# mainboard.net
KiCad netlist of a schematic drawn in EAGLE
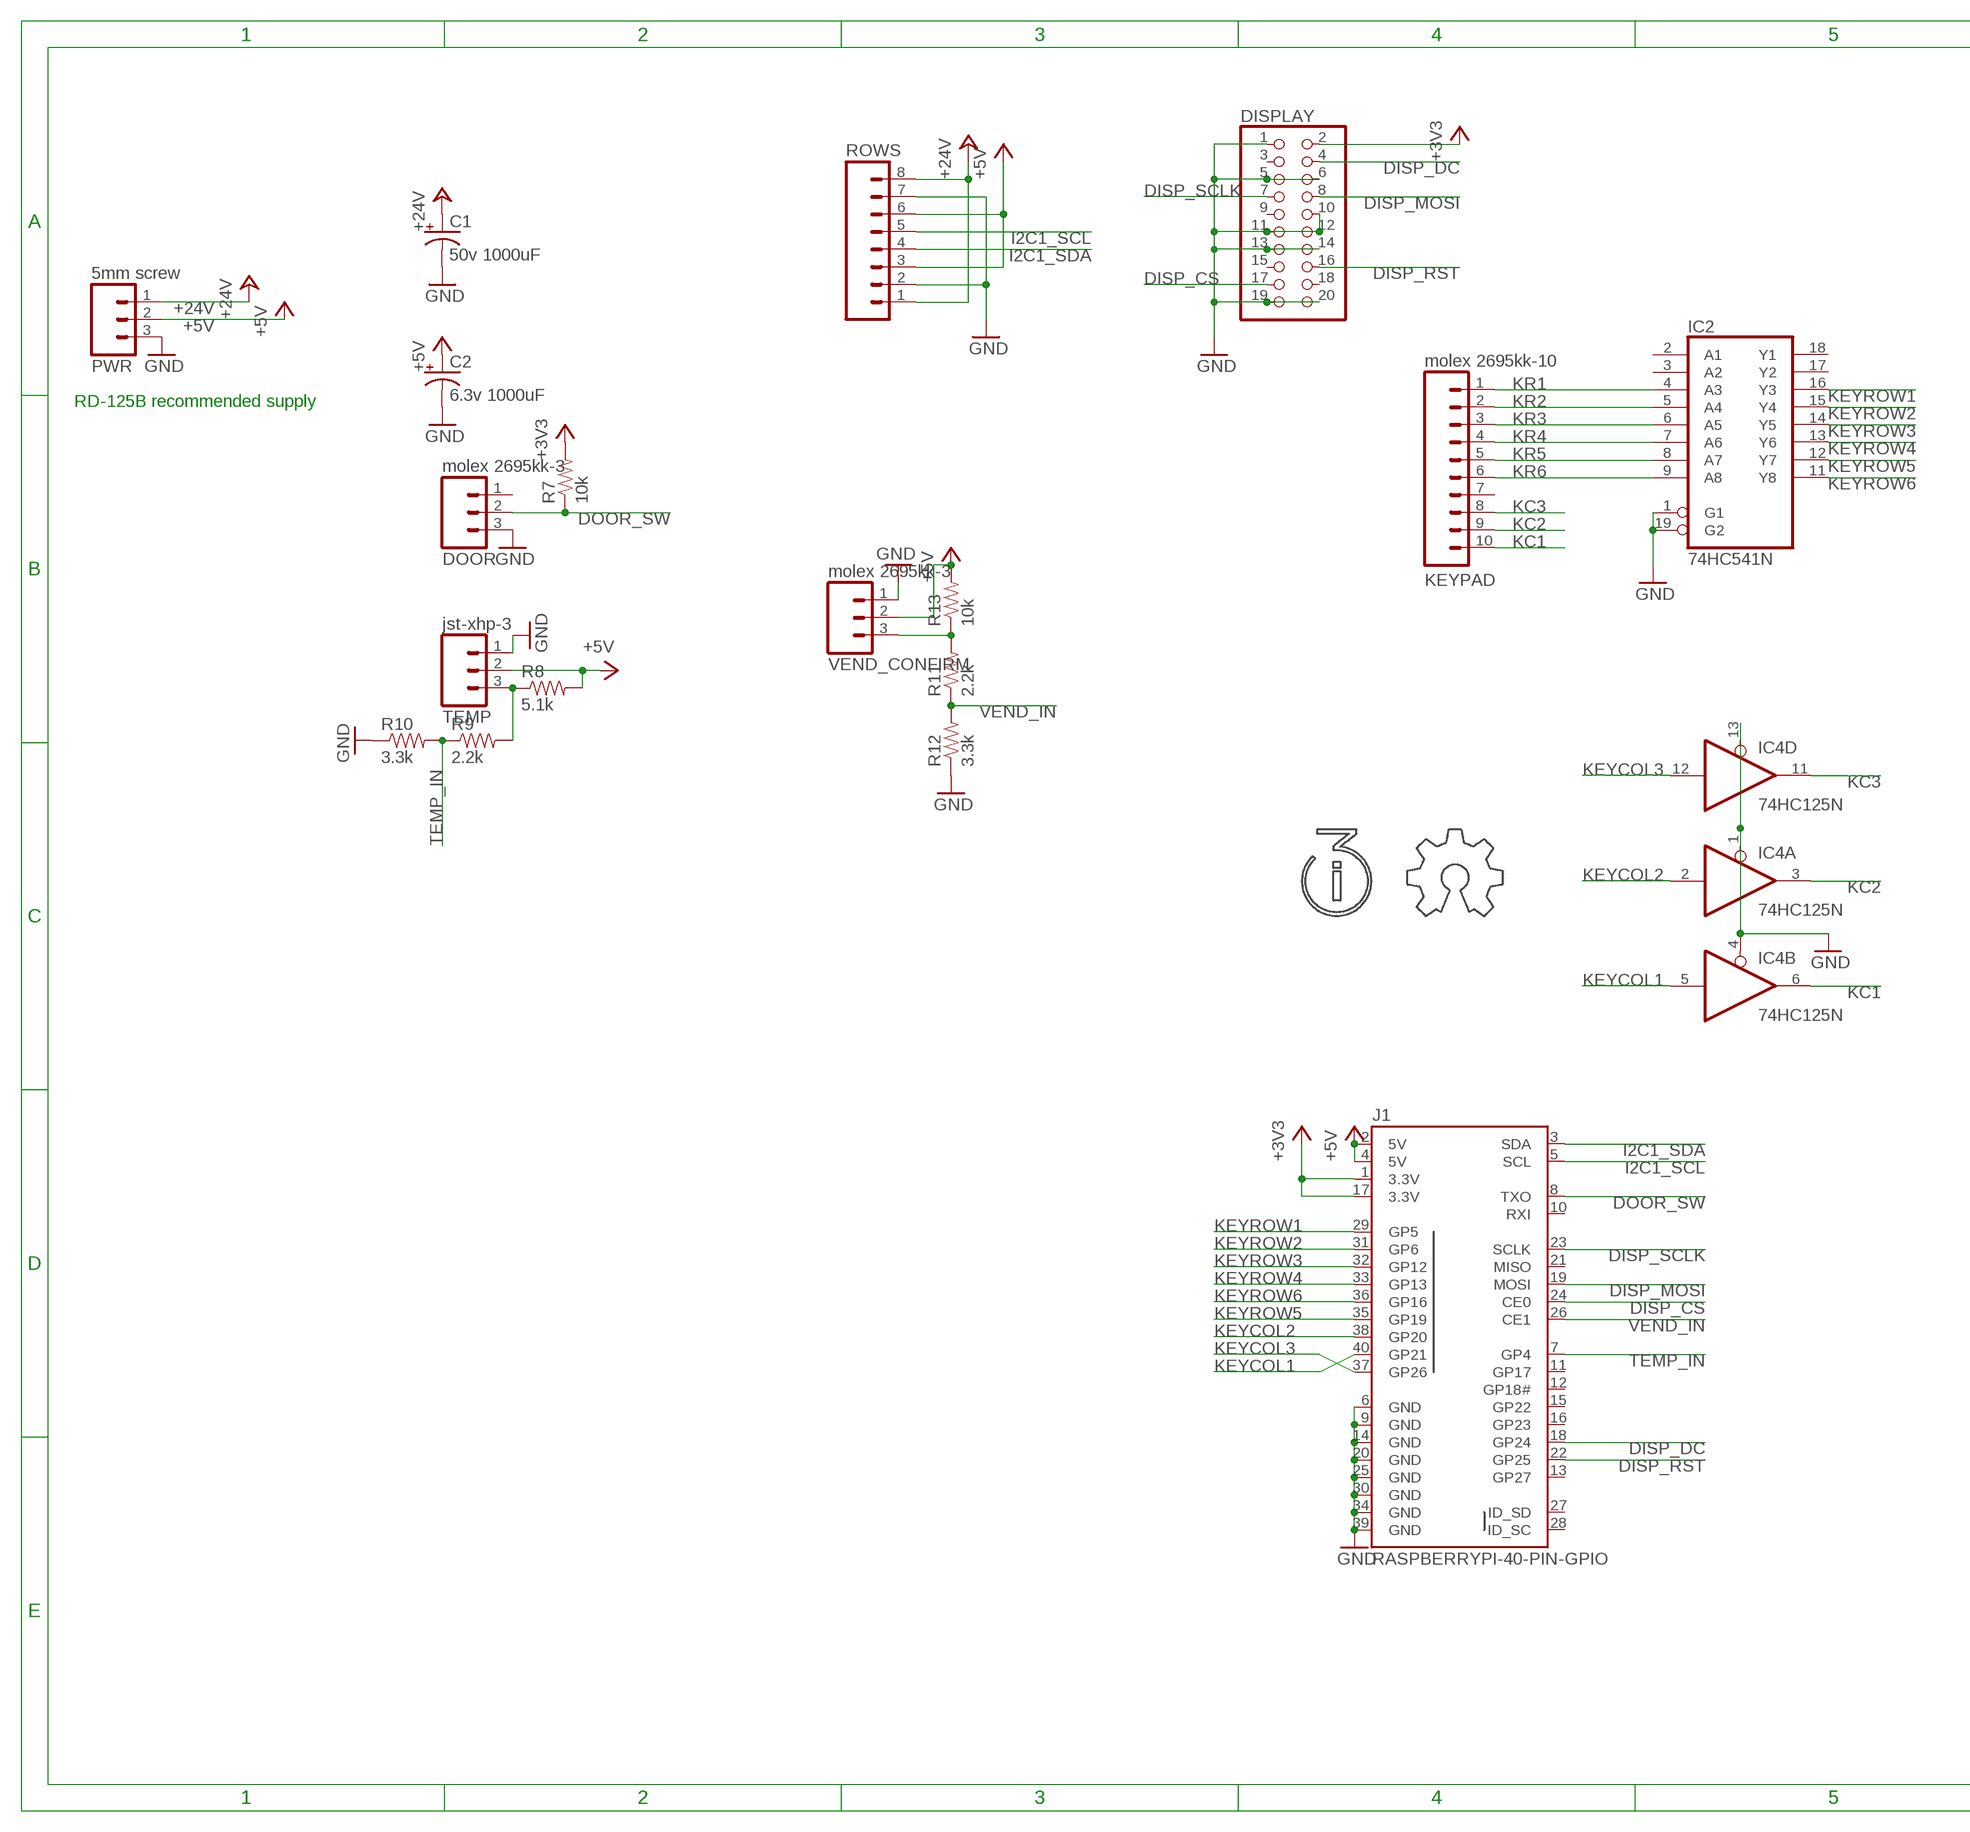
[diagram p0: schematic, sheet 1, part 1 of 2]
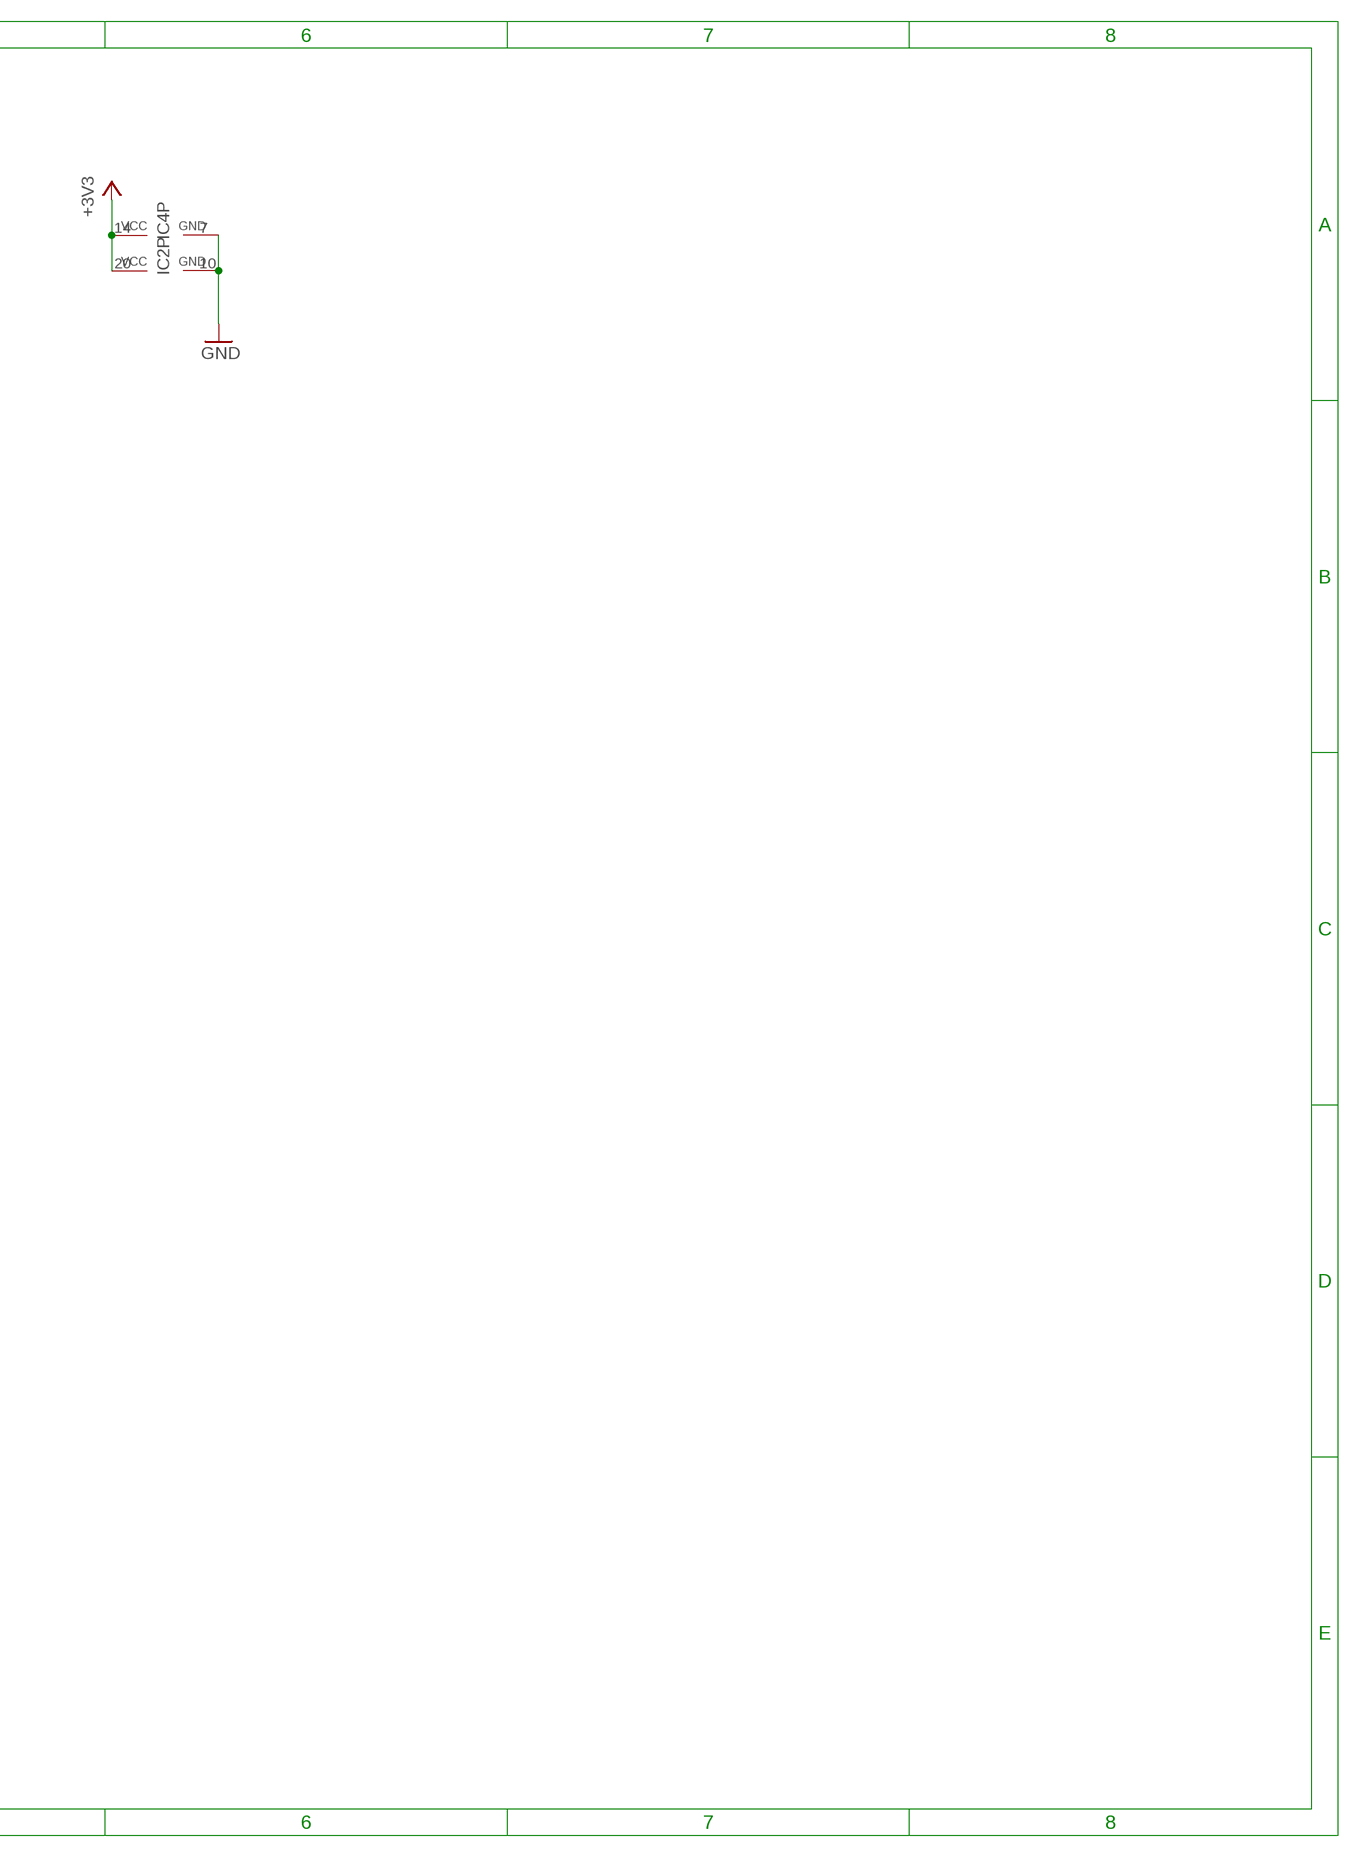
[diagram p1: schematic, sheet 1, part 2 of 2]

(export (version "E")
  (design (tool "Eeschema 10.0.6"))
  (components
    (comp (ref "C1")
      (value "50v 1000uF")
      (footprint "eagle-import:CPOL-RADIAL-1000UF-25V")
      (libsource (lib "eagle-import") (part "CAP_POLPTH4"))
    )
    (comp (ref "C2")
      (value "6.3v 1000uF")
      (footprint "eagle-import:CPOL-RADIAL-1000UF-25V")
      (libsource (lib "eagle-import") (part "CAP_POLPTH4"))
    )
    (comp (ref "DISPLAY")
      (value "PINHD-2X10")
      (footprint "eagle-import:2X10")
      (libsource (lib "eagle-import") (part "PINHD-2X10"))
    )
    (comp (ref "DOOR")
      (value "molex 2695kk-3")
      (footprint "eagle-import:MOLEX-1X3")
      (libsource (lib "eagle-import") (part "M03POLAR"))
    )
    (comp (ref "IC2")
      (value "74HC541N")
      (footprint "eagle-import:DIL20")
      (libsource (lib "eagle-import") (part "74541NHC"))
    )
    (comp (ref "IC4")
      (value "74HC125N")
      (footprint "eagle-import:DIL14")
      (libsource (lib "eagle-import") (part "74125NHC"))
    )
    (comp (ref "J1")
      (value "RASPBERRYPI-40-PIN-GPIO")
      (footprint "eagle-import:2X20-SHROUDED")
      (libsource (lib "eagle-import") (part "RASPBERRYPI-40-PIN-GPIO"))
    )
    (comp (ref "KEYPAD")
      (value "molex 2695kk-10")
      (footprint "eagle-import:1X10_LOCK")
      (libsource (lib "eagle-import") (part "M10LOCK"))
    )
    (comp (ref "PWR")
      (value "5mm screw")
      (footprint "eagle-import:SCREWTERMINAL-5MM-3")
      (libsource (lib "eagle-import") (part "M03-SCREW-5MM"))
    )
    (comp (ref "R7")
      (value "10k")
      (footprint "eagle-import:1206")
      (libsource (lib "eagle-import") (part "RESISTOR1206"))
    )
    (comp (ref "R8")
      (value "5.1k")
      (footprint "eagle-import:1206")
      (libsource (lib "eagle-import") (part "RESISTOR1206"))
    )
    (comp (ref "R9")
      (value "2.2k")
      (footprint "eagle-import:1206")
      (libsource (lib "eagle-import") (part "RESISTOR1206"))
    )
    (comp (ref "R10")
      (value "3.3k")
      (footprint "eagle-import:1206")
      (libsource (lib "eagle-import") (part "RESISTOR1206"))
    )
    (comp (ref "R11")
      (value "2.2k")
      (footprint "eagle-import:1206")
      (libsource (lib "eagle-import") (part "RESISTOR1206"))
    )
    (comp (ref "R12")
      (value "3.3k")
      (footprint "eagle-import:1206")
      (libsource (lib "eagle-import") (part "RESISTOR1206"))
    )
    (comp (ref "R13")
      (value "10k")
      (footprint "eagle-import:1206")
      (libsource (lib "eagle-import") (part "RESISTOR1206"))
    )
    (comp (ref "ROWS")
      (value "M08FEMALE_LOCK")
      (footprint "eagle-import:1X08_FEMALE_LOCK")
      (libsource (lib "eagle-import") (part "M08FEMALE_LOCK"))
    )
    (comp (ref "TEMP")
      (value "jst-xhp-3")
      (footprint "eagle-import:1X03")
      (libsource (lib "eagle-import") (part "M03PTH"))
    )
    (comp (ref "U$1")
      (value "I3LOGO")
      (footprint "eagle-import:I3LOGO")
      (libsource (lib "eagle-import") (part "I3LOGO"))
    )
    (comp (ref "U$2")
      (value "OSHWLOGO")
      (footprint "eagle-import:OSHWLOGO")
      (libsource (lib "eagle-import") (part "OSHWLOGO"))
    )
    (comp (ref "VEND_CONFIRM")
      (value "molex 2695kk-3")
      (footprint "eagle-import:MOLEX-1X3")
      (libsource (lib "eagle-import") (part "M03POLAR"))
    )
  )
  (nets
    (net (code "1") (name "+3V3") (class "Default")
      (node (ref "DISPLAY") (pin "2") (pinfunction "2_2") (pintype "passive"))
      (node (ref "IC2") (pin "20") (pinfunction "VCC_20") (pintype "power_in"))
      (node (ref "IC4") (pin "14") (pinfunction "VCC_14") (pintype "power_in"))
      (node (ref "J1") (pin "1") (pinfunction "3.3V_1") (pintype "power_in"))
      (node (ref "J1") (pin "17") (pinfunction "3.3V_17") (pintype "power_in"))
      (node (ref "R7") (pin "2") (pinfunction "2_2") (pintype "passive"))
    )
    (net (code "2") (name "+5V") (class "Default")
      (node (ref "C2") (pin "+") (pinfunction "+_+") (pintype "passive"))
      (node (ref "J1") (pin "2") (pinfunction "5V_2") (pintype "power_in"))
      (node (ref "J1") (pin "4") (pinfunction "5V_4") (pintype "power_in"))
      (node (ref "PWR") (pin "2") (pinfunction "2_2") (pintype "passive"))
      (node (ref "R13") (pin "2") (pinfunction "2_2") (pintype "passive"))
      (node (ref "R8") (pin "2") (pinfunction "2_2") (pintype "passive"))
      (node (ref "ROWS") (pin "3") (pinfunction "3_3") (pintype "passive"))
      (node (ref "ROWS") (pin "6") (pinfunction "6_6") (pintype "passive"))
      (node (ref "TEMP") (pin "2") (pinfunction "2_2") (pintype "passive"))
      (node (ref "VEND_CONFIRM") (pin "2") (pinfunction "2_2") (pintype "passive"))
    )
    (net (code "3") (name "+24V") (class "Default")
      (node (ref "C1") (pin "+") (pinfunction "+_+") (pintype "passive"))
      (node (ref "PWR") (pin "1") (pinfunction "1_1") (pintype "passive"))
      (node (ref "ROWS") (pin "1") (pinfunction "1_1") (pintype "passive"))
      (node (ref "ROWS") (pin "8") (pinfunction "8_8") (pintype "passive"))
    )
    (net (code "4") (name "/DISP_CS") (class "Default")
      (node (ref "DISPLAY") (pin "17") (pinfunction "17_17") (pintype "passive"))
      (node (ref "J1") (pin "24") (pinfunction "CE0_24") (pintype "output"))
    )
    (net (code "5") (name "/DISP_DC") (class "Default")
      (node (ref "DISPLAY") (pin "4") (pinfunction "4_4") (pintype "passive"))
      (node (ref "J1") (pin "18") (pinfunction "GP24_18") (pintype "bidirectional"))
    )
    (net (code "6") (name "/DISP_MOSI") (class "Default")
      (node (ref "DISPLAY") (pin "8") (pinfunction "8_8") (pintype "passive"))
      (node (ref "J1") (pin "19") (pinfunction "MOSI_19") (pintype "output"))
    )
    (net (code "7") (name "/DISP_RST") (class "Default")
      (node (ref "DISPLAY") (pin "16") (pinfunction "16_16") (pintype "passive"))
      (node (ref "J1") (pin "22") (pinfunction "GP25_22") (pintype "bidirectional"))
    )
    (net (code "8") (name "/DISP_SCLK") (class "Default")
      (node (ref "DISPLAY") (pin "7") (pinfunction "7_7") (pintype "passive"))
      (node (ref "J1") (pin "23") (pinfunction "SCLK_23") (pintype "output"))
    )
    (net (code "9") (name "/DOOR_SW") (class "Default")
      (node (ref "DOOR") (pin "2") (pinfunction "2_2") (pintype "passive"))
      (node (ref "J1") (pin "8") (pinfunction "TXO_8") (pintype "output"))
      (node (ref "R7") (pin "1") (pinfunction "1_1") (pintype "passive"))
    )
    (net (code "10") (name "/I2C1_SCL") (class "Default")
      (node (ref "J1") (pin "5") (pinfunction "SCL_5") (pintype "bidirectional"))
      (node (ref "ROWS") (pin "5") (pinfunction "5_5") (pintype "passive"))
    )
    (net (code "11") (name "/I2C1_SDA") (class "Default")
      (node (ref "J1") (pin "3") (pinfunction "SDA_3") (pintype "bidirectional"))
      (node (ref "ROWS") (pin "4") (pinfunction "4_4") (pintype "passive"))
    )
    (net (code "12") (name "/KC1") (class "Default")
      (node (ref "IC4") (pin "6") (pinfunction "O_6") (pintype "tri_state"))
      (node (ref "KEYPAD") (pin "10") (pinfunction "10_10") (pintype "passive"))
    )
    (net (code "13") (name "/KC2") (class "Default")
      (node (ref "IC4") (pin "3") (pinfunction "O_3") (pintype "tri_state"))
      (node (ref "KEYPAD") (pin "9") (pinfunction "9_9") (pintype "passive"))
    )
    (net (code "14") (name "/KC3") (class "Default")
      (node (ref "IC4") (pin "11") (pinfunction "O_11") (pintype "tri_state"))
      (node (ref "KEYPAD") (pin "8") (pinfunction "8_8") (pintype "passive"))
    )
    (net (code "15") (name "/KEYCOL1") (class "Default")
      (node (ref "IC4") (pin "5") (pinfunction "I_5") (pintype "input"))
      (node (ref "J1") (pin "40") (pinfunction "GP21_40") (pintype "bidirectional"))
    )
    (net (code "16") (name "/KEYCOL2") (class "Default")
      (node (ref "IC4") (pin "2") (pinfunction "I_2") (pintype "input"))
      (node (ref "J1") (pin "38") (pinfunction "GP20_38") (pintype "bidirectional"))
    )
    (net (code "17") (name "/KEYCOL3") (class "Default")
      (node (ref "IC4") (pin "12") (pinfunction "I_12") (pintype "input"))
      (node (ref "J1") (pin "37") (pinfunction "GP26_37") (pintype "bidirectional"))
    )
    (net (code "18") (name "/KEYROW1") (class "Default")
      (node (ref "IC2") (pin "16") (pinfunction "Y3_16") (pintype "tri_state"))
      (node (ref "J1") (pin "29") (pinfunction "GP5_29") (pintype "bidirectional"))
    )
    (net (code "19") (name "/KEYROW2") (class "Default")
      (node (ref "IC2") (pin "15") (pinfunction "Y4_15") (pintype "tri_state"))
      (node (ref "J1") (pin "31") (pinfunction "GP6_31") (pintype "bidirectional"))
    )
    (net (code "20") (name "/KEYROW3") (class "Default")
      (node (ref "IC2") (pin "14") (pinfunction "Y5_14") (pintype "tri_state"))
      (node (ref "J1") (pin "32") (pinfunction "GP12_32") (pintype "bidirectional"))
    )
    (net (code "21") (name "/KEYROW4") (class "Default")
      (node (ref "IC2") (pin "13") (pinfunction "Y6_13") (pintype "tri_state"))
      (node (ref "J1") (pin "33") (pinfunction "GP13_33") (pintype "bidirectional"))
    )
    (net (code "22") (name "/KEYROW5") (class "Default")
      (node (ref "IC2") (pin "12") (pinfunction "Y7_12") (pintype "tri_state"))
      (node (ref "J1") (pin "35") (pinfunction "GP19_35") (pintype "bidirectional"))
    )
    (net (code "23") (name "/KEYROW6") (class "Default")
      (node (ref "IC2") (pin "11") (pinfunction "Y8_11") (pintype "tri_state"))
      (node (ref "J1") (pin "36") (pinfunction "GP16_36") (pintype "bidirectional"))
    )
    (net (code "24") (name "/KR1") (class "Default")
      (node (ref "IC2") (pin "4") (pinfunction "A3_4") (pintype "input"))
      (node (ref "KEYPAD") (pin "1") (pinfunction "1_1") (pintype "passive"))
    )
    (net (code "25") (name "/KR2") (class "Default")
      (node (ref "IC2") (pin "5") (pinfunction "A4_5") (pintype "input"))
      (node (ref "KEYPAD") (pin "2") (pinfunction "2_2") (pintype "passive"))
    )
    (net (code "26") (name "/KR3") (class "Default")
      (node (ref "IC2") (pin "6") (pinfunction "A5_6") (pintype "input"))
      (node (ref "KEYPAD") (pin "3") (pinfunction "3_3") (pintype "passive"))
    )
    (net (code "27") (name "/KR4") (class "Default")
      (node (ref "IC2") (pin "7") (pinfunction "A6_7") (pintype "input"))
      (node (ref "KEYPAD") (pin "4") (pinfunction "4_4") (pintype "passive"))
    )
    (net (code "28") (name "/KR5") (class "Default")
      (node (ref "IC2") (pin "8") (pinfunction "A7_8") (pintype "input"))
      (node (ref "KEYPAD") (pin "5") (pinfunction "5_5") (pintype "passive"))
    )
    (net (code "29") (name "/KR6") (class "Default")
      (node (ref "IC2") (pin "9") (pinfunction "A8_9") (pintype "input"))
      (node (ref "KEYPAD") (pin "6") (pinfunction "6_6") (pintype "passive"))
    )
    (net (code "30") (name "/TEMP_IN") (class "Default")
      (node (ref "J1") (pin "7") (pinfunction "GP4_7") (pintype "bidirectional"))
      (node (ref "R10") (pin "2") (pinfunction "2_2") (pintype "passive"))
      (node (ref "R9") (pin "1") (pinfunction "1_1") (pintype "passive"))
    )
    (net (code "31") (name "/VEND_IN") (class "Default")
      (node (ref "J1") (pin "26") (pinfunction "CE1_26") (pintype "output"))
      (node (ref "R11") (pin "1") (pinfunction "1_1") (pintype "passive"))
      (node (ref "R12") (pin "2") (pinfunction "2_2") (pintype "passive"))
    )
    (net (code "32") (name "GND") (class "Default")
      (node (ref "C1") (pin "-") (pinfunction "-_-") (pintype "passive"))
      (node (ref "C2") (pin "-") (pinfunction "-_-") (pintype "passive"))
      (node (ref "DISPLAY") (pin "1") (pinfunction "1_1") (pintype "passive"))
      (node (ref "DISPLAY") (pin "10") (pinfunction "10_10") (pintype "passive"))
      (node (ref "DISPLAY") (pin "11") (pinfunction "11_11") (pintype "passive"))
      (node (ref "DISPLAY") (pin "12") (pinfunction "12_12") (pintype "passive"))
      (node (ref "DISPLAY") (pin "13") (pinfunction "13_13") (pintype "passive"))
      (node (ref "DISPLAY") (pin "14") (pinfunction "14_14") (pintype "passive"))
      (node (ref "DISPLAY") (pin "19") (pinfunction "19_19") (pintype "passive"))
      (node (ref "DISPLAY") (pin "20") (pinfunction "20_20") (pintype "passive"))
      (node (ref "DISPLAY") (pin "5") (pinfunction "5_5") (pintype "passive"))
      (node (ref "DISPLAY") (pin "6") (pinfunction "6_6") (pintype "passive"))
      (node (ref "DOOR") (pin "3") (pinfunction "3_3") (pintype "passive"))
      (node (ref "IC2") (pin "1") (pinfunction "G1_1") (pintype "input"))
      (node (ref "IC2") (pin "10") (pinfunction "GND_10") (pintype "power_in"))
      (node (ref "IC2") (pin "19") (pinfunction "G2_19") (pintype "input"))
      (node (ref "IC4") (pin "1") (pinfunction "OE_1") (pintype "input"))
      (node (ref "IC4") (pin "13") (pinfunction "OE_13") (pintype "input"))
      (node (ref "IC4") (pin "4") (pinfunction "OE_4") (pintype "input"))
      (node (ref "IC4") (pin "7") (pinfunction "GND_7") (pintype "power_in"))
      (node (ref "J1") (pin "14") (pinfunction "GND_14") (pintype "power_in"))
      (node (ref "J1") (pin "20") (pinfunction "GND_20") (pintype "power_in"))
      (node (ref "J1") (pin "25") (pinfunction "GND_25") (pintype "power_in"))
      (node (ref "J1") (pin "30") (pinfunction "GND_30") (pintype "power_in"))
      (node (ref "J1") (pin "34") (pinfunction "GND_34") (pintype "power_in"))
      (node (ref "J1") (pin "39") (pinfunction "GND_39") (pintype "power_in"))
      (node (ref "J1") (pin "6") (pinfunction "GND_6") (pintype "power_in"))
      (node (ref "J1") (pin "9") (pinfunction "GND_9") (pintype "power_in"))
      (node (ref "PWR") (pin "3") (pinfunction "3_3") (pintype "passive"))
      (node (ref "R10") (pin "1") (pinfunction "1_1") (pintype "passive"))
      (node (ref "R12") (pin "1") (pinfunction "1_1") (pintype "passive"))
      (node (ref "ROWS") (pin "2") (pinfunction "2_2") (pintype "passive"))
      (node (ref "ROWS") (pin "7") (pinfunction "7_7") (pintype "passive"))
      (node (ref "TEMP") (pin "1") (pinfunction "1_1") (pintype "passive"))
      (node (ref "VEND_CONFIRM") (pin "1") (pinfunction "1_1") (pintype "passive"))
    )
    (net (code "33") (name "Net-(R8-Pad1)") (class "Default")
      (node (ref "R8") (pin "1") (pinfunction "1_1") (pintype "passive"))
      (node (ref "R9") (pin "2") (pinfunction "2_2") (pintype "passive"))
      (node (ref "TEMP") (pin "3") (pinfunction "3_3") (pintype "passive"))
    )
    (net (code "34") (name "Net-(R11-Pad2)") (class "Default")
      (node (ref "R11") (pin "2") (pinfunction "2_2") (pintype "passive"))
      (node (ref "R13") (pin "1") (pinfunction "1_1") (pintype "passive"))
      (node (ref "VEND_CONFIRM") (pin "3") (pinfunction "3_3") (pintype "passive"))
    )
    (net (code "35") (name "unconnected-(DISPLAY-Pad3)") (class "Default")
      (node (ref "DISPLAY") (pin "3") (pinfunction "3_3") (pintype "passive"))
    )
    (net (code "36") (name "unconnected-(DISPLAY-Pad9)") (class "Default")
      (node (ref "DISPLAY") (pin "9") (pinfunction "9_9") (pintype "passive"))
    )
    (net (code "37") (name "unconnected-(DISPLAY-Pad15)") (class "Default")
      (node (ref "DISPLAY") (pin "15") (pinfunction "15_15") (pintype "passive"))
    )
    (net (code "38") (name "unconnected-(DISPLAY-Pad18)") (class "Default")
      (node (ref "DISPLAY") (pin "18") (pinfunction "18_18") (pintype "passive"))
    )
    (net (code "39") (name "unconnected-(DOOR-Pad1)") (class "Default")
      (node (ref "DOOR") (pin "1") (pinfunction "1_1") (pintype "passive"))
    )
    (net (code "40") (name "unconnected-(IC2A-A1-Pad2)") (class "Default")
      (node (ref "IC2") (pin "2") (pinfunction "A1_2") (pintype "input"))
    )
    (net (code "41") (name "unconnected-(IC2A-A2-Pad3)") (class "Default")
      (node (ref "IC2") (pin "3") (pinfunction "A2_3") (pintype "input"))
    )
    (net (code "42") (name "unconnected-(IC2A-Y1-Pad18)") (class "Default")
      (node (ref "IC2") (pin "18") (pinfunction "Y1_18") (pintype "tri_state"))
    )
    (net (code "43") (name "unconnected-(IC2A-Y2-Pad17)") (class "Default")
      (node (ref "IC2") (pin "17") (pinfunction "Y2_17") (pintype "tri_state"))
    )
    (net (code "44") (name "unconnected-(J1-GP17-Pad11)") (class "Default")
      (node (ref "J1") (pin "11") (pinfunction "GP17_11") (pintype "bidirectional"))
    )
    (net (code "45") (name "unconnected-(J1-GP18#-Pad12)") (class "Default")
      (node (ref "J1") (pin "12") (pinfunction "GP18#_12") (pintype "bidirectional"))
    )
    (net (code "46") (name "unconnected-(J1-GP22-Pad15)") (class "Default")
      (node (ref "J1") (pin "15") (pinfunction "GP22_15") (pintype "bidirectional"))
    )
    (net (code "47") (name "unconnected-(J1-GP23-Pad16)") (class "Default")
      (node (ref "J1") (pin "16") (pinfunction "GP23_16") (pintype "bidirectional"))
    )
    (net (code "48") (name "unconnected-(J1-GP27-Pad13)") (class "Default")
      (node (ref "J1") (pin "13") (pinfunction "GP27_13") (pintype "bidirectional"))
    )
    (net (code "49") (name "unconnected-(J1-ID_SC-Pad28)") (class "Default")
      (node (ref "J1") (pin "28") (pinfunction "ID_SC_28") (pintype "bidirectional"))
    )
    (net (code "50") (name "unconnected-(J1-ID_SD-Pad27)") (class "Default")
      (node (ref "J1") (pin "27") (pinfunction "ID_SD_27") (pintype "bidirectional"))
    )
    (net (code "51") (name "unconnected-(J1-MISO-Pad21)") (class "Default")
      (node (ref "J1") (pin "21") (pinfunction "MISO_21") (pintype "input"))
    )
    (net (code "52") (name "unconnected-(J1-RXI-Pad10)") (class "Default")
      (node (ref "J1") (pin "10") (pinfunction "RXI_10") (pintype "input"))
    )
    (net (code "53") (name "unconnected-(KEYPAD-Pad7)") (class "Default")
      (node (ref "KEYPAD") (pin "7") (pinfunction "7_7") (pintype "passive"))
    )
  )
)
